# PatchPanel2015.net
KiCad netlist of a schematic drawn in EAGLE
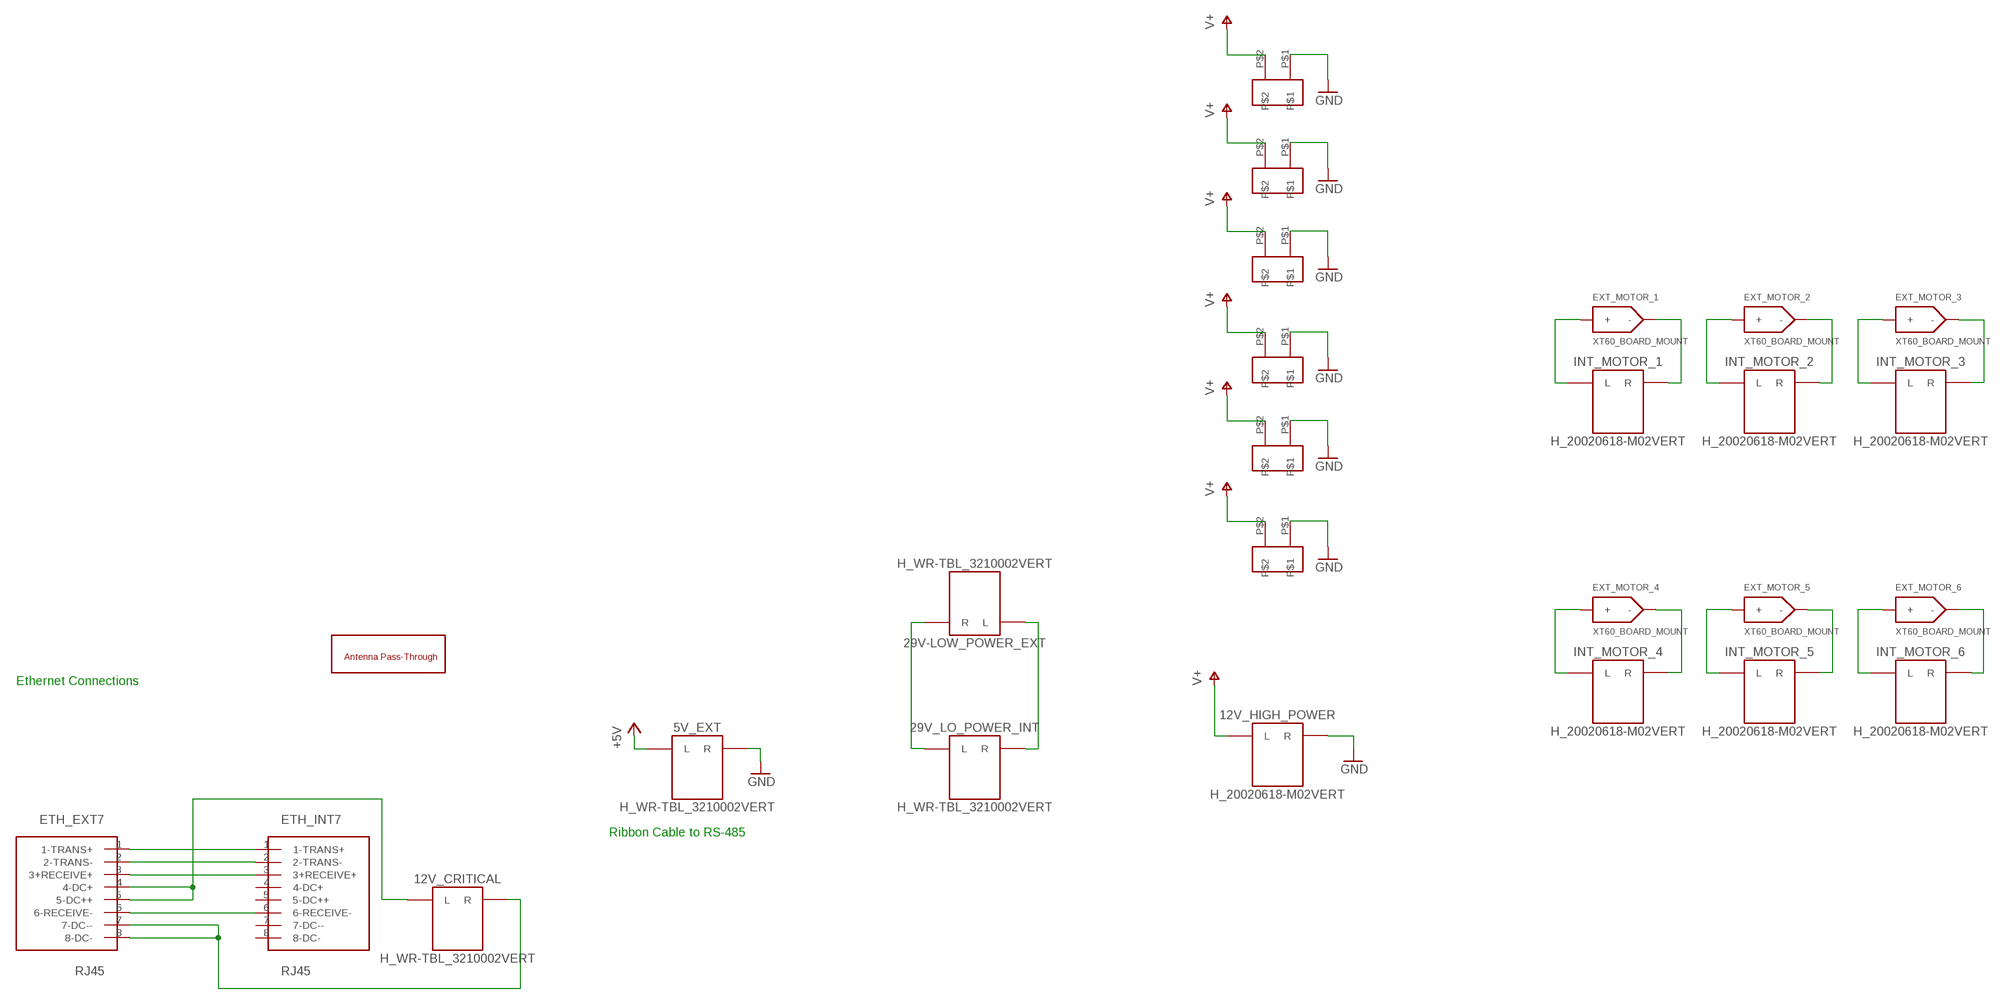
[diagram p0: schematic, sheet 1, part 1 of 2]
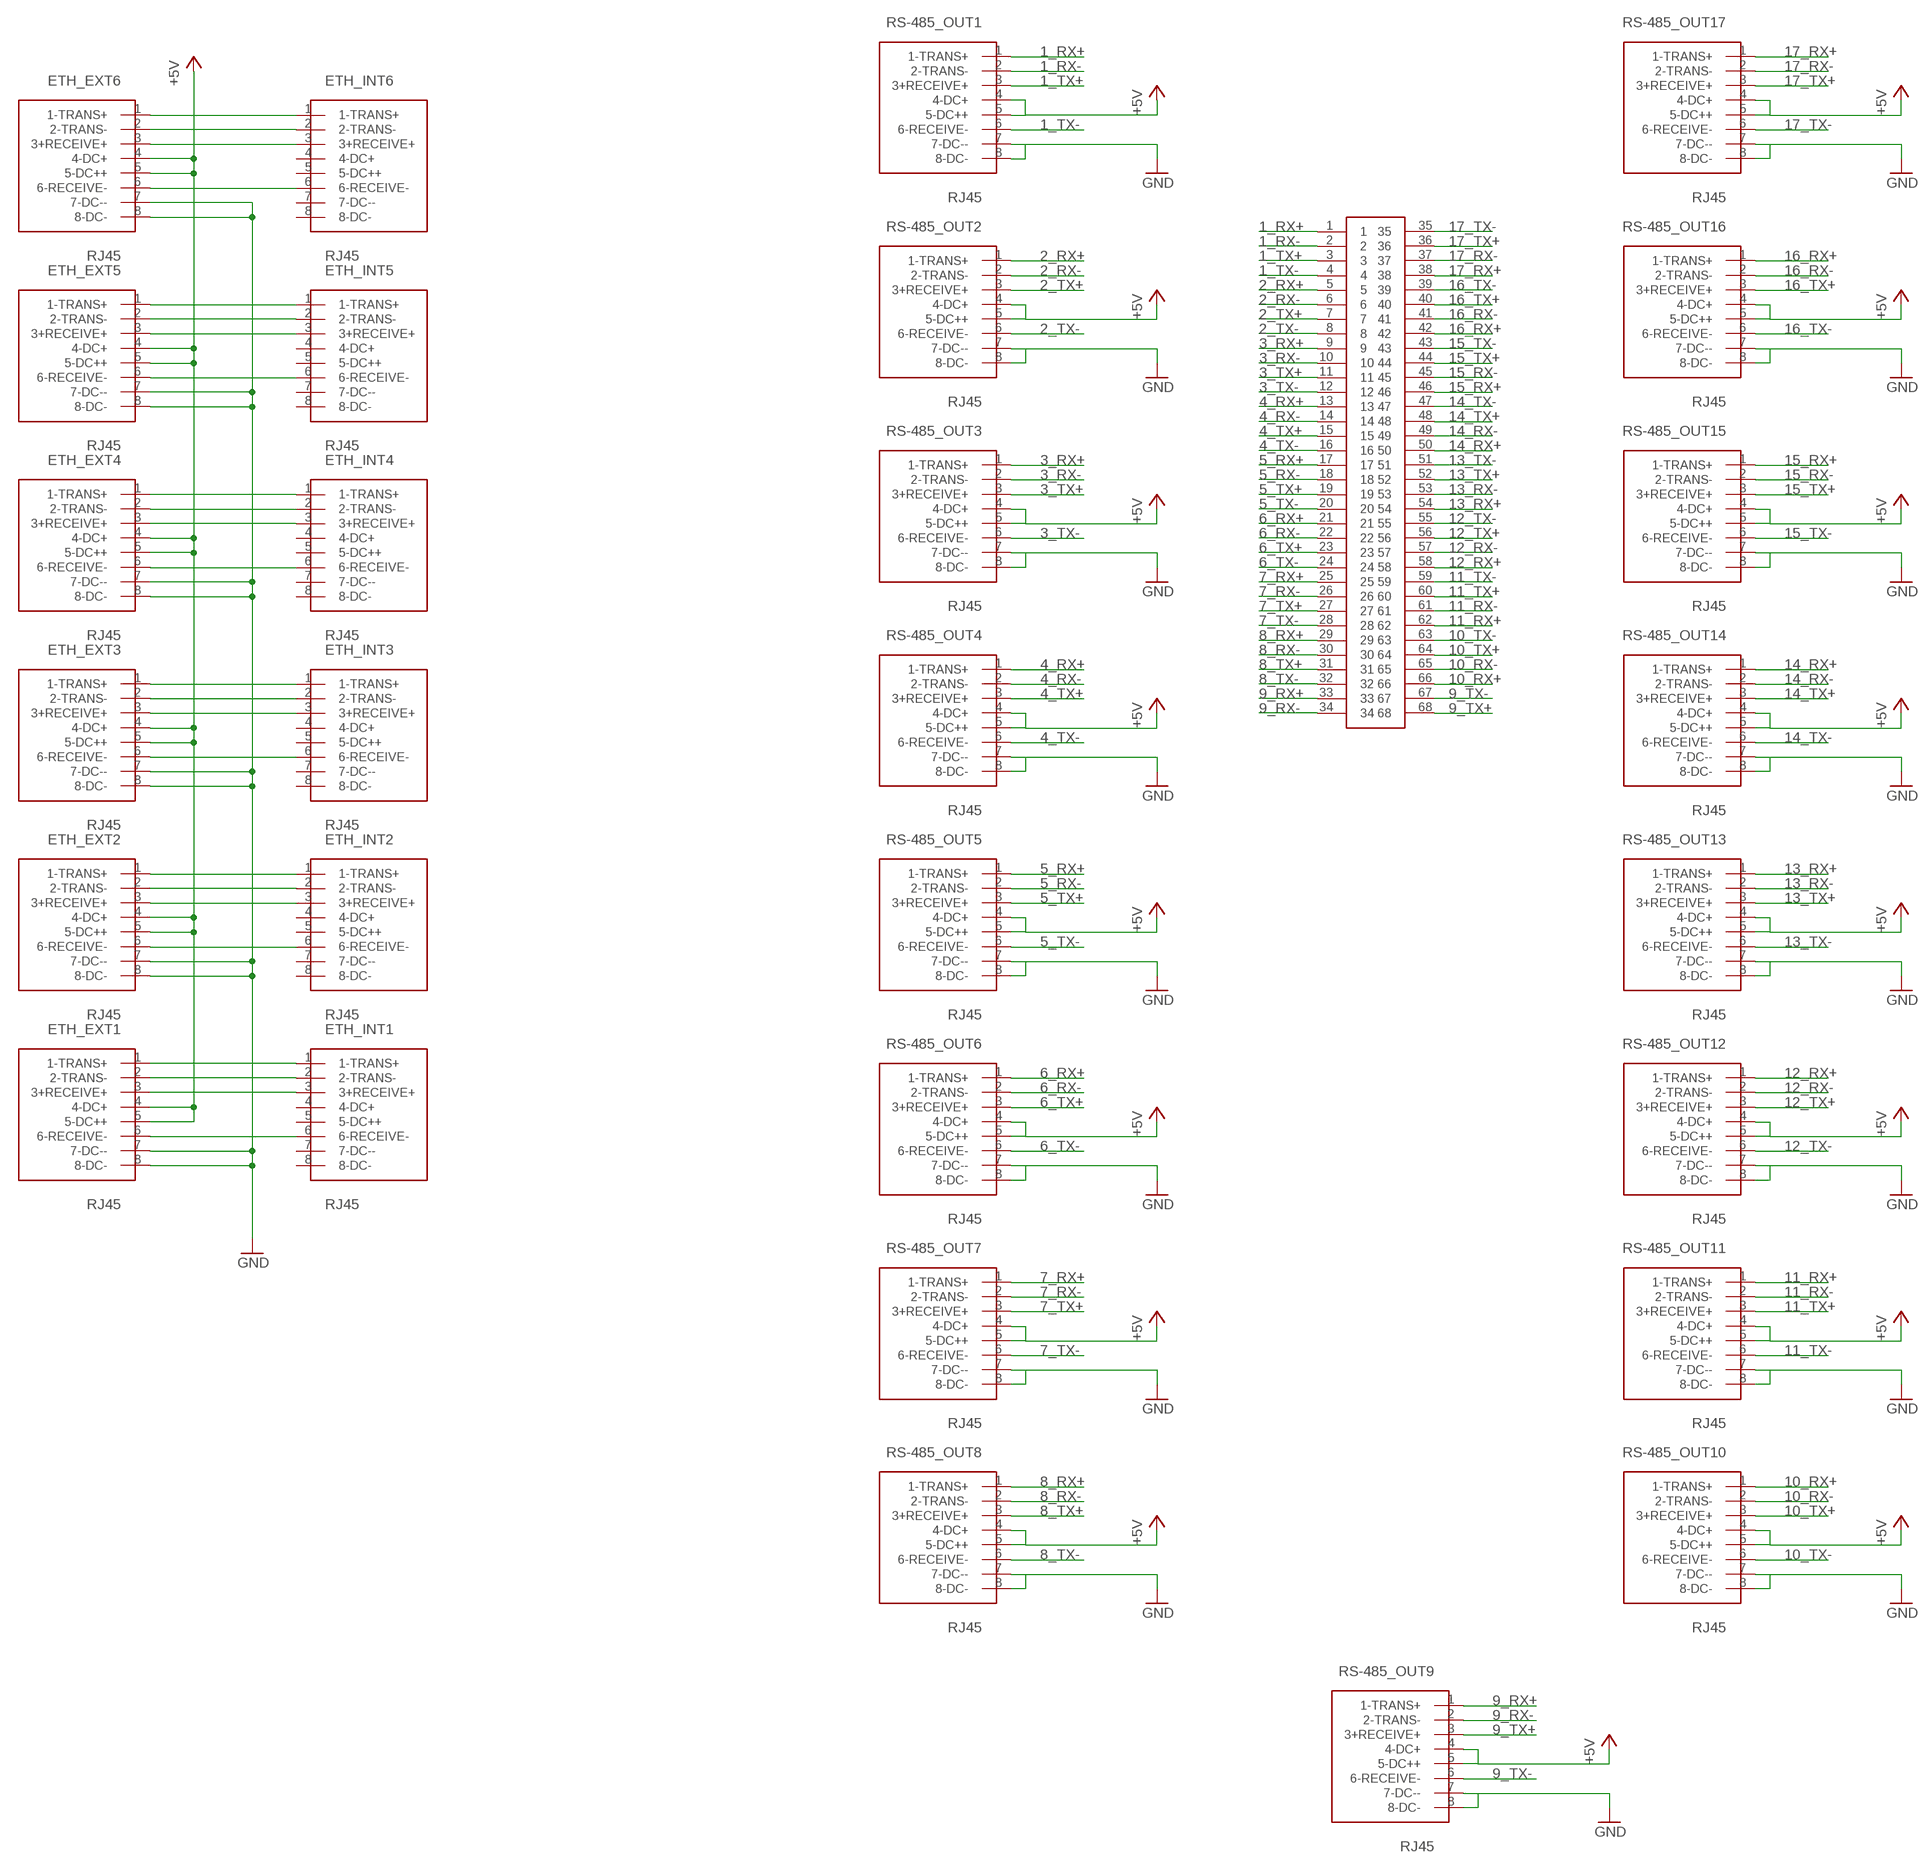
[diagram p1: schematic, sheet 1, part 2 of 2]

(export (version "E")
  (design (tool "Eeschema 10.0.6"))
  (components
    (comp (ref "5V_EXT")
      (value "H_WR-TBL_3210002VERT")
      (footprint "eagle-import:691321100002")
      (libsource (lib "eagle-import") (part "H_WR-TBL_3210002VERT"))
    )
    (comp (ref "12V_CRITICAL")
      (value "H_WR-TBL_3210002VERT")
      (footprint "eagle-import:691321100002")
      (libsource (lib "eagle-import") (part "H_WR-TBL_3210002VERT"))
    )
    (comp (ref "12V_HIGH_POWER")
      (value "H_20020618-M02VERT")
      (footprint "eagle-import:20020620-M02")
      (libsource (lib "eagle-import") (part "H_20020618-M02VERT"))
    )
    (comp (ref "29V-LOW_POWER_EXT")
      (value "H_WR-TBL_3210002VERT")
      (footprint "eagle-import:691321100002")
      (libsource (lib "eagle-import") (part "H_WR-TBL_3210002VERT"))
    )
    (comp (ref "29V_LO_POWER_INT")
      (value "H_WR-TBL_3210002VERT")
      (footprint "eagle-import:691321100002")
      (libsource (lib "eagle-import") (part "H_WR-TBL_3210002VERT"))
    )
    (comp (ref "ETH_EXT1")
      (value "RJ45")
      (footprint "eagle-import:RJ45-CAT5E")
      (libsource (lib "eagle-import") (part "RJ45"))
    )
    (comp (ref "ETH_EXT2")
      (value "RJ45")
      (footprint "eagle-import:RJ45-CAT5E")
      (libsource (lib "eagle-import") (part "RJ45"))
    )
    (comp (ref "ETH_EXT3")
      (value "RJ45")
      (footprint "eagle-import:RJ45-CAT5E")
      (libsource (lib "eagle-import") (part "RJ45"))
    )
    (comp (ref "ETH_EXT4")
      (value "RJ45")
      (footprint "eagle-import:RJ45-CAT5E")
      (libsource (lib "eagle-import") (part "RJ45"))
    )
    (comp (ref "ETH_EXT5")
      (value "RJ45")
      (footprint "eagle-import:RJ45-CAT5E")
      (libsource (lib "eagle-import") (part "RJ45"))
    )
    (comp (ref "ETH_EXT6")
      (value "RJ45")
      (footprint "eagle-import:RJ45-CAT5E")
      (libsource (lib "eagle-import") (part "RJ45"))
    )
    (comp (ref "ETH_EXT7")
      (value "RJ45")
      (footprint "eagle-import:RJ45-CAT5E")
      (libsource (lib "eagle-import") (part "RJ45"))
    )
    (comp (ref "ETH_INT1")
      (value "RJ45")
      (footprint "eagle-import:RJ45-CAT5E")
      (libsource (lib "eagle-import") (part "RJ45"))
    )
    (comp (ref "ETH_INT2")
      (value "RJ45")
      (footprint "eagle-import:RJ45-CAT5E")
      (libsource (lib "eagle-import") (part "RJ45"))
    )
    (comp (ref "ETH_INT3")
      (value "RJ45")
      (footprint "eagle-import:RJ45-CAT5E")
      (libsource (lib "eagle-import") (part "RJ45"))
    )
    (comp (ref "ETH_INT4")
      (value "RJ45")
      (footprint "eagle-import:RJ45-CAT5E")
      (libsource (lib "eagle-import") (part "RJ45"))
    )
    (comp (ref "ETH_INT5")
      (value "RJ45")
      (footprint "eagle-import:RJ45-CAT5E")
      (libsource (lib "eagle-import") (part "RJ45"))
    )
    (comp (ref "ETH_INT6")
      (value "RJ45")
      (footprint "eagle-import:RJ45-CAT5E")
      (libsource (lib "eagle-import") (part "RJ45"))
    )
    (comp (ref "ETH_INT7")
      (value "RJ45")
      (footprint "eagle-import:RJ45-CAT5E")
      (libsource (lib "eagle-import") (part "RJ45"))
    )
    (comp (ref "EXT_MOTOR_1")
      (value "XT60_BOARD_MOUNT")
      (footprint "eagle-import:XT60_BOARD")
      (libsource (lib "eagle-import") (part "XT60_BOARD_MOUNT"))
    )
    (comp (ref "EXT_MOTOR_2")
      (value "XT60_BOARD_MOUNT")
      (footprint "eagle-import:XT60_BOARD")
      (libsource (lib "eagle-import") (part "XT60_BOARD_MOUNT"))
    )
    (comp (ref "EXT_MOTOR_3")
      (value "XT60_BOARD_MOUNT")
      (footprint "eagle-import:XT60_BOARD")
      (libsource (lib "eagle-import") (part "XT60_BOARD_MOUNT"))
    )
    (comp (ref "EXT_MOTOR_4")
      (value "XT60_BOARD_MOUNT")
      (footprint "eagle-import:XT60_BOARD")
      (libsource (lib "eagle-import") (part "XT60_BOARD_MOUNT"))
    )
    (comp (ref "EXT_MOTOR_5")
      (value "XT60_BOARD_MOUNT")
      (footprint "eagle-import:XT60_BOARD")
      (libsource (lib "eagle-import") (part "XT60_BOARD_MOUNT"))
    )
    (comp (ref "EXT_MOTOR_6")
      (value "XT60_BOARD_MOUNT")
      (footprint "eagle-import:XT60_BOARD")
      (libsource (lib "eagle-import") (part "XT60_BOARD_MOUNT"))
    )
    (comp (ref "INT_MOTOR_1")
      (value "H_20020618-M02VERT")
      (footprint "eagle-import:20020620-M02")
      (libsource (lib "eagle-import") (part "H_20020618-M02VERT"))
    )
    (comp (ref "INT_MOTOR_2")
      (value "H_20020618-M02VERT")
      (footprint "eagle-import:20020620-M02")
      (libsource (lib "eagle-import") (part "H_20020618-M02VERT"))
    )
    (comp (ref "INT_MOTOR_3")
      (value "H_20020618-M02VERT")
      (footprint "eagle-import:20020620-M02")
      (libsource (lib "eagle-import") (part "H_20020618-M02VERT"))
    )
    (comp (ref "INT_MOTOR_4")
      (value "H_20020618-M02VERT")
      (footprint "eagle-import:20020620-M02")
      (libsource (lib "eagle-import") (part "H_20020618-M02VERT"))
    )
    (comp (ref "INT_MOTOR_5")
      (value "H_20020618-M02VERT")
      (footprint "eagle-import:20020620-M02")
      (libsource (lib "eagle-import") (part "H_20020618-M02VERT"))
    )
    (comp (ref "INT_MOTOR_6")
      (value "H_20020618-M02VERT")
      (footprint "eagle-import:20020620-M02")
      (libsource (lib "eagle-import") (part "H_20020618-M02VERT"))
    )
    (comp (ref "RS-485_OUT1")
      (value "RJ45")
      (footprint "eagle-import:RJ45-CAT5E")
      (libsource (lib "eagle-import") (part "RJ45"))
    )
    (comp (ref "RS-485_OUT2")
      (value "RJ45")
      (footprint "eagle-import:RJ45-CAT5E")
      (libsource (lib "eagle-import") (part "RJ45"))
    )
    (comp (ref "RS-485_OUT3")
      (value "RJ45")
      (footprint "eagle-import:RJ45-CAT5E")
      (libsource (lib "eagle-import") (part "RJ45"))
    )
    (comp (ref "RS-485_OUT4")
      (value "RJ45")
      (footprint "eagle-import:RJ45-CAT5E")
      (libsource (lib "eagle-import") (part "RJ45"))
    )
    (comp (ref "RS-485_OUT5")
      (value "RJ45")
      (footprint "eagle-import:RJ45-CAT5E")
      (libsource (lib "eagle-import") (part "RJ45"))
    )
    (comp (ref "RS-485_OUT6")
      (value "RJ45")
      (footprint "eagle-import:RJ45-CAT5E")
      (libsource (lib "eagle-import") (part "RJ45"))
    )
    (comp (ref "RS-485_OUT7")
      (value "RJ45")
      (footprint "eagle-import:RJ45-CAT5E")
      (libsource (lib "eagle-import") (part "RJ45"))
    )
    (comp (ref "RS-485_OUT8")
      (value "RJ45")
      (footprint "eagle-import:RJ45-CAT5E")
      (libsource (lib "eagle-import") (part "RJ45"))
    )
    (comp (ref "RS-485_OUT9")
      (value "RJ45")
      (footprint "eagle-import:RJ45-CAT5E")
      (libsource (lib "eagle-import") (part "RJ45"))
    )
    (comp (ref "RS-485_OUT10")
      (value "RJ45")
      (footprint "eagle-import:RJ45-CAT5E")
      (libsource (lib "eagle-import") (part "RJ45"))
    )
    (comp (ref "RS-485_OUT11")
      (value "RJ45")
      (footprint "eagle-import:RJ45-CAT5E")
      (libsource (lib "eagle-import") (part "RJ45"))
    )
    (comp (ref "RS-485_OUT12")
      (value "RJ45")
      (footprint "eagle-import:RJ45-CAT5E")
      (libsource (lib "eagle-import") (part "RJ45"))
    )
    (comp (ref "RS-485_OUT13")
      (value "RJ45")
      (footprint "eagle-import:RJ45-CAT5E")
      (libsource (lib "eagle-import") (part "RJ45"))
    )
    (comp (ref "RS-485_OUT14")
      (value "RJ45")
      (footprint "eagle-import:RJ45-CAT5E")
      (libsource (lib "eagle-import") (part "RJ45"))
    )
    (comp (ref "RS-485_OUT15")
      (value "RJ45")
      (footprint "eagle-import:RJ45-CAT5E")
      (libsource (lib "eagle-import") (part "RJ45"))
    )
    (comp (ref "RS-485_OUT16")
      (value "RJ45")
      (footprint "eagle-import:RJ45-CAT5E")
      (libsource (lib "eagle-import") (part "RJ45"))
    )
    (comp (ref "RS-485_OUT17")
      (value "RJ45")
      (footprint "eagle-import:RJ45-CAT5E")
      (libsource (lib "eagle-import") (part "RJ45"))
    )
    (comp (ref "U$1")
      (value "MLX-2")
      (footprint "eagle-import:42002-2")
      (libsource (lib "eagle-import") (part "MLX-2"))
    )
    (comp (ref "U$2")
      (value "MLX-2")
      (footprint "eagle-import:42002-2")
      (libsource (lib "eagle-import") (part "MLX-2"))
    )
    (comp (ref "U$3")
      (value "MLX-2")
      (footprint "eagle-import:42002-2")
      (libsource (lib "eagle-import") (part "MLX-2"))
    )
    (comp (ref "U$4")
      (value "TB60050685100")
      (footprint "eagle-import:60050685100")
      (libsource (lib "eagle-import") (part "TB60050685100"))
    )
    (comp (ref "U$5")
      (value "MLX-2")
      (footprint "eagle-import:42002-2")
      (libsource (lib "eagle-import") (part "MLX-2"))
    )
    (comp (ref "U$6")
      (value "MLX-2")
      (footprint "eagle-import:42002-2")
      (libsource (lib "eagle-import") (part "MLX-2"))
    )
    (comp (ref "U$8")
      (value "MLX-2")
      (footprint "eagle-import:42002-2")
      (libsource (lib "eagle-import") (part "MLX-2"))
    )
    (comp (ref "U$16")
      (value "SMA-THRU")
      (footprint "eagle-import:SMA")
      (libsource (lib "eagle-import") (part "SMA-THRU"))
    )
  )
  (nets
    (net (code "1") (name "+5V") (class "Default")
      (node (ref "5V_EXT") (pin "L") (pinfunction "L_L") (pintype "bidirectional"))
      (node (ref "ETH_EXT1") (pin "4") (pinfunction "4-DC+_4") (pintype "bidirectional"))
      (node (ref "ETH_EXT1") (pin "5") (pinfunction "5-DC++_5") (pintype "bidirectional"))
      (node (ref "ETH_EXT2") (pin "4") (pinfunction "4-DC+_4") (pintype "bidirectional"))
      (node (ref "ETH_EXT2") (pin "5") (pinfunction "5-DC++_5") (pintype "bidirectional"))
      (node (ref "ETH_EXT3") (pin "4") (pinfunction "4-DC+_4") (pintype "bidirectional"))
      (node (ref "ETH_EXT3") (pin "5") (pinfunction "5-DC++_5") (pintype "bidirectional"))
      (node (ref "ETH_EXT4") (pin "4") (pinfunction "4-DC+_4") (pintype "bidirectional"))
      (node (ref "ETH_EXT4") (pin "5") (pinfunction "5-DC++_5") (pintype "bidirectional"))
      (node (ref "ETH_EXT5") (pin "4") (pinfunction "4-DC+_4") (pintype "bidirectional"))
      (node (ref "ETH_EXT5") (pin "5") (pinfunction "5-DC++_5") (pintype "bidirectional"))
      (node (ref "ETH_EXT6") (pin "4") (pinfunction "4-DC+_4") (pintype "bidirectional"))
      (node (ref "ETH_EXT6") (pin "5") (pinfunction "5-DC++_5") (pintype "bidirectional"))
      (node (ref "RS-485_OUT1") (pin "4") (pinfunction "4-DC+_4") (pintype "bidirectional"))
      (node (ref "RS-485_OUT1") (pin "5") (pinfunction "5-DC++_5") (pintype "bidirectional"))
      (node (ref "RS-485_OUT10") (pin "4") (pinfunction "4-DC+_4") (pintype "bidirectional"))
      (node (ref "RS-485_OUT10") (pin "5") (pinfunction "5-DC++_5") (pintype "bidirectional"))
      (node (ref "RS-485_OUT11") (pin "4") (pinfunction "4-DC+_4") (pintype "bidirectional"))
      (node (ref "RS-485_OUT11") (pin "5") (pinfunction "5-DC++_5") (pintype "bidirectional"))
      (node (ref "RS-485_OUT12") (pin "4") (pinfunction "4-DC+_4") (pintype "bidirectional"))
      (node (ref "RS-485_OUT12") (pin "5") (pinfunction "5-DC++_5") (pintype "bidirectional"))
      (node (ref "RS-485_OUT13") (pin "4") (pinfunction "4-DC+_4") (pintype "bidirectional"))
      (node (ref "RS-485_OUT13") (pin "5") (pinfunction "5-DC++_5") (pintype "bidirectional"))
      (node (ref "RS-485_OUT14") (pin "4") (pinfunction "4-DC+_4") (pintype "bidirectional"))
      (node (ref "RS-485_OUT14") (pin "5") (pinfunction "5-DC++_5") (pintype "bidirectional"))
      (node (ref "RS-485_OUT15") (pin "4") (pinfunction "4-DC+_4") (pintype "bidirectional"))
      (node (ref "RS-485_OUT15") (pin "5") (pinfunction "5-DC++_5") (pintype "bidirectional"))
      (node (ref "RS-485_OUT16") (pin "4") (pinfunction "4-DC+_4") (pintype "bidirectional"))
      (node (ref "RS-485_OUT16") (pin "5") (pinfunction "5-DC++_5") (pintype "bidirectional"))
      (node (ref "RS-485_OUT17") (pin "4") (pinfunction "4-DC+_4") (pintype "bidirectional"))
      (node (ref "RS-485_OUT17") (pin "5") (pinfunction "5-DC++_5") (pintype "bidirectional"))
      (node (ref "RS-485_OUT2") (pin "4") (pinfunction "4-DC+_4") (pintype "bidirectional"))
      (node (ref "RS-485_OUT2") (pin "5") (pinfunction "5-DC++_5") (pintype "bidirectional"))
      (node (ref "RS-485_OUT3") (pin "4") (pinfunction "4-DC+_4") (pintype "bidirectional"))
      (node (ref "RS-485_OUT3") (pin "5") (pinfunction "5-DC++_5") (pintype "bidirectional"))
      (node (ref "RS-485_OUT4") (pin "4") (pinfunction "4-DC+_4") (pintype "bidirectional"))
      (node (ref "RS-485_OUT4") (pin "5") (pinfunction "5-DC++_5") (pintype "bidirectional"))
      (node (ref "RS-485_OUT5") (pin "4") (pinfunction "4-DC+_4") (pintype "bidirectional"))
      (node (ref "RS-485_OUT5") (pin "5") (pinfunction "5-DC++_5") (pintype "bidirectional"))
      (node (ref "RS-485_OUT6") (pin "4") (pinfunction "4-DC+_4") (pintype "bidirectional"))
      (node (ref "RS-485_OUT6") (pin "5") (pinfunction "5-DC++_5") (pintype "bidirectional"))
      (node (ref "RS-485_OUT7") (pin "4") (pinfunction "4-DC+_4") (pintype "bidirectional"))
      (node (ref "RS-485_OUT7") (pin "5") (pinfunction "5-DC++_5") (pintype "bidirectional"))
      (node (ref "RS-485_OUT8") (pin "4") (pinfunction "4-DC+_4") (pintype "bidirectional"))
      (node (ref "RS-485_OUT8") (pin "5") (pinfunction "5-DC++_5") (pintype "bidirectional"))
      (node (ref "RS-485_OUT9") (pin "4") (pinfunction "4-DC+_4") (pintype "bidirectional"))
      (node (ref "RS-485_OUT9") (pin "5") (pinfunction "5-DC++_5") (pintype "bidirectional"))
    )
    (net (code "2") (name "/1_RX+") (class "Default")
      (node (ref "RS-485_OUT1") (pin "1") (pinfunction "1-TRANS+_1") (pintype "bidirectional"))
      (node (ref "U$4") (pin "1") (pinfunction "1_1") (pintype "bidirectional"))
    )
    (net (code "3") (name "/1_RX-") (class "Default")
      (node (ref "RS-485_OUT1") (pin "2") (pinfunction "2-TRANS-_2") (pintype "bidirectional"))
      (node (ref "U$4") (pin "2") (pinfunction "2_2") (pintype "bidirectional"))
    )
    (net (code "4") (name "/1_TX+") (class "Default")
      (node (ref "RS-485_OUT1") (pin "3") (pinfunction "3+RECEIVE+_3") (pintype "bidirectional"))
      (node (ref "U$4") (pin "3") (pinfunction "3_3") (pintype "bidirectional"))
    )
    (net (code "5") (name "/1_TX-") (class "Default")
      (node (ref "RS-485_OUT1") (pin "6") (pinfunction "6-RECEIVE-_6") (pintype "bidirectional"))
      (node (ref "U$4") (pin "4") (pinfunction "4_4") (pintype "bidirectional"))
    )
    (net (code "6") (name "/2_RX+") (class "Default")
      (node (ref "RS-485_OUT2") (pin "1") (pinfunction "1-TRANS+_1") (pintype "bidirectional"))
      (node (ref "U$4") (pin "5") (pinfunction "5_5") (pintype "bidirectional"))
    )
    (net (code "7") (name "/2_RX-") (class "Default")
      (node (ref "RS-485_OUT2") (pin "2") (pinfunction "2-TRANS-_2") (pintype "bidirectional"))
      (node (ref "U$4") (pin "6") (pinfunction "6_6") (pintype "bidirectional"))
    )
    (net (code "8") (name "/2_TX+") (class "Default")
      (node (ref "RS-485_OUT2") (pin "3") (pinfunction "3+RECEIVE+_3") (pintype "bidirectional"))
      (node (ref "U$4") (pin "7") (pinfunction "7_7") (pintype "bidirectional"))
    )
    (net (code "9") (name "/2_TX-") (class "Default")
      (node (ref "RS-485_OUT2") (pin "6") (pinfunction "6-RECEIVE-_6") (pintype "bidirectional"))
      (node (ref "U$4") (pin "8") (pinfunction "8_8") (pintype "bidirectional"))
    )
    (net (code "10") (name "/3_RX+") (class "Default")
      (node (ref "RS-485_OUT3") (pin "1") (pinfunction "1-TRANS+_1") (pintype "bidirectional"))
      (node (ref "U$4") (pin "9") (pinfunction "9_9") (pintype "bidirectional"))
    )
    (net (code "11") (name "/3_RX-") (class "Default")
      (node (ref "RS-485_OUT3") (pin "2") (pinfunction "2-TRANS-_2") (pintype "bidirectional"))
      (node (ref "U$4") (pin "10") (pinfunction "10_10") (pintype "bidirectional"))
    )
    (net (code "12") (name "/3_TX+") (class "Default")
      (node (ref "RS-485_OUT3") (pin "3") (pinfunction "3+RECEIVE+_3") (pintype "bidirectional"))
      (node (ref "U$4") (pin "11") (pinfunction "11_11") (pintype "bidirectional"))
    )
    (net (code "13") (name "/3_TX-") (class "Default")
      (node (ref "RS-485_OUT3") (pin "6") (pinfunction "6-RECEIVE-_6") (pintype "bidirectional"))
      (node (ref "U$4") (pin "12") (pinfunction "12_12") (pintype "bidirectional"))
    )
    (net (code "14") (name "/4_RX+") (class "Default")
      (node (ref "RS-485_OUT4") (pin "1") (pinfunction "1-TRANS+_1") (pintype "bidirectional"))
      (node (ref "U$4") (pin "13") (pinfunction "13_13") (pintype "bidirectional"))
    )
    (net (code "15") (name "/4_RX-") (class "Default")
      (node (ref "RS-485_OUT4") (pin "2") (pinfunction "2-TRANS-_2") (pintype "bidirectional"))
      (node (ref "U$4") (pin "14") (pinfunction "14_14") (pintype "bidirectional"))
    )
    (net (code "16") (name "/4_TX+") (class "Default")
      (node (ref "RS-485_OUT4") (pin "3") (pinfunction "3+RECEIVE+_3") (pintype "bidirectional"))
      (node (ref "U$4") (pin "15") (pinfunction "15_15") (pintype "bidirectional"))
    )
    (net (code "17") (name "/4_TX-") (class "Default")
      (node (ref "RS-485_OUT4") (pin "6") (pinfunction "6-RECEIVE-_6") (pintype "bidirectional"))
      (node (ref "U$4") (pin "16") (pinfunction "16_16") (pintype "bidirectional"))
    )
    (net (code "18") (name "/5_RX+") (class "Default")
      (node (ref "RS-485_OUT5") (pin "1") (pinfunction "1-TRANS+_1") (pintype "bidirectional"))
      (node (ref "U$4") (pin "17") (pinfunction "17_17") (pintype "bidirectional"))
    )
    (net (code "19") (name "/5_RX-") (class "Default")
      (node (ref "RS-485_OUT5") (pin "2") (pinfunction "2-TRANS-_2") (pintype "bidirectional"))
      (node (ref "U$4") (pin "18") (pinfunction "18_18") (pintype "bidirectional"))
    )
    (net (code "20") (name "/5_TX+") (class "Default")
      (node (ref "RS-485_OUT5") (pin "3") (pinfunction "3+RECEIVE+_3") (pintype "bidirectional"))
      (node (ref "U$4") (pin "19") (pinfunction "19_19") (pintype "bidirectional"))
    )
    (net (code "21") (name "/5_TX-") (class "Default")
      (node (ref "RS-485_OUT5") (pin "6") (pinfunction "6-RECEIVE-_6") (pintype "bidirectional"))
      (node (ref "U$4") (pin "20") (pinfunction "20_20") (pintype "bidirectional"))
    )
    (net (code "22") (name "/6_RX+") (class "Default")
      (node (ref "RS-485_OUT6") (pin "1") (pinfunction "1-TRANS+_1") (pintype "bidirectional"))
      (node (ref "U$4") (pin "21") (pinfunction "21_21") (pintype "bidirectional"))
    )
    (net (code "23") (name "/6_RX-") (class "Default")
      (node (ref "RS-485_OUT6") (pin "2") (pinfunction "2-TRANS-_2") (pintype "bidirectional"))
      (node (ref "U$4") (pin "22") (pinfunction "22_22") (pintype "bidirectional"))
    )
    (net (code "24") (name "/6_TX+") (class "Default")
      (node (ref "RS-485_OUT6") (pin "3") (pinfunction "3+RECEIVE+_3") (pintype "bidirectional"))
      (node (ref "U$4") (pin "23") (pinfunction "23_23") (pintype "bidirectional"))
    )
    (net (code "25") (name "/6_TX-") (class "Default")
      (node (ref "RS-485_OUT6") (pin "6") (pinfunction "6-RECEIVE-_6") (pintype "bidirectional"))
      (node (ref "U$4") (pin "24") (pinfunction "24_24") (pintype "bidirectional"))
    )
    (net (code "26") (name "/7_RX+") (class "Default")
      (node (ref "RS-485_OUT7") (pin "1") (pinfunction "1-TRANS+_1") (pintype "bidirectional"))
      (node (ref "U$4") (pin "25") (pinfunction "25_25") (pintype "bidirectional"))
    )
    (net (code "27") (name "/7_RX-") (class "Default")
      (node (ref "RS-485_OUT7") (pin "2") (pinfunction "2-TRANS-_2") (pintype "bidirectional"))
      (node (ref "U$4") (pin "26") (pinfunction "26_26") (pintype "bidirectional"))
    )
    (net (code "28") (name "/7_TX+") (class "Default")
      (node (ref "RS-485_OUT7") (pin "3") (pinfunction "3+RECEIVE+_3") (pintype "bidirectional"))
      (node (ref "U$4") (pin "27") (pinfunction "27_27") (pintype "bidirectional"))
    )
    (net (code "29") (name "/7_TX-") (class "Default")
      (node (ref "RS-485_OUT7") (pin "6") (pinfunction "6-RECEIVE-_6") (pintype "bidirectional"))
      (node (ref "U$4") (pin "28") (pinfunction "28_28") (pintype "bidirectional"))
    )
    (net (code "30") (name "/8_RX+") (class "Default")
      (node (ref "RS-485_OUT8") (pin "1") (pinfunction "1-TRANS+_1") (pintype "bidirectional"))
      (node (ref "U$4") (pin "29") (pinfunction "29_29") (pintype "bidirectional"))
    )
    (net (code "31") (name "/8_RX-") (class "Default")
      (node (ref "RS-485_OUT8") (pin "2") (pinfunction "2-TRANS-_2") (pintype "bidirectional"))
      (node (ref "U$4") (pin "30") (pinfunction "30_30") (pintype "bidirectional"))
    )
    (net (code "32") (name "/8_TX+") (class "Default")
      (node (ref "RS-485_OUT8") (pin "3") (pinfunction "3+RECEIVE+_3") (pintype "bidirectional"))
      (node (ref "U$4") (pin "31") (pinfunction "31_31") (pintype "bidirectional"))
    )
    (net (code "33") (name "/8_TX-") (class "Default")
      (node (ref "RS-485_OUT8") (pin "6") (pinfunction "6-RECEIVE-_6") (pintype "bidirectional"))
      (node (ref "U$4") (pin "32") (pinfunction "32_32") (pintype "bidirectional"))
    )
    (net (code "34") (name "/9_RX+") (class "Default")
      (node (ref "RS-485_OUT9") (pin "1") (pinfunction "1-TRANS+_1") (pintype "bidirectional"))
      (node (ref "U$4") (pin "33") (pinfunction "33_33") (pintype "bidirectional"))
    )
    (net (code "35") (name "/9_RX-") (class "Default")
      (node (ref "RS-485_OUT9") (pin "2") (pinfunction "2-TRANS-_2") (pintype "bidirectional"))
      (node (ref "U$4") (pin "34") (pinfunction "34_34") (pintype "bidirectional"))
    )
    (net (code "36") (name "/9_TX+") (class "Default")
      (node (ref "RS-485_OUT9") (pin "3") (pinfunction "3+RECEIVE+_3") (pintype "bidirectional"))
      (node (ref "U$4") (pin "68") (pinfunction "68_68") (pintype "bidirectional"))
    )
    (net (code "37") (name "/9_TX-") (class "Default")
      (node (ref "RS-485_OUT9") (pin "6") (pinfunction "6-RECEIVE-_6") (pintype "bidirectional"))
      (node (ref "U$4") (pin "67") (pinfunction "67_67") (pintype "bidirectional"))
    )
    (net (code "38") (name "/10_RX+") (class "Default")
      (node (ref "RS-485_OUT10") (pin "1") (pinfunction "1-TRANS+_1") (pintype "bidirectional"))
      (node (ref "U$4") (pin "66") (pinfunction "66_66") (pintype "bidirectional"))
    )
    (net (code "39") (name "/10_RX-") (class "Default")
      (node (ref "RS-485_OUT10") (pin "2") (pinfunction "2-TRANS-_2") (pintype "bidirectional"))
      (node (ref "U$4") (pin "65") (pinfunction "65_65") (pintype "bidirectional"))
    )
    (net (code "40") (name "/10_TX+") (class "Default")
      (node (ref "RS-485_OUT10") (pin "3") (pinfunction "3+RECEIVE+_3") (pintype "bidirectional"))
      (node (ref "U$4") (pin "64") (pinfunction "64_64") (pintype "bidirectional"))
    )
    (net (code "41") (name "/10_TX-") (class "Default")
      (node (ref "RS-485_OUT10") (pin "6") (pinfunction "6-RECEIVE-_6") (pintype "bidirectional"))
      (node (ref "U$4") (pin "63") (pinfunction "63_63") (pintype "bidirectional"))
    )
    (net (code "42") (name "/11_RX+") (class "Default")
      (node (ref "RS-485_OUT11") (pin "1") (pinfunction "1-TRANS+_1") (pintype "bidirectional"))
      (node (ref "U$4") (pin "62") (pinfunction "62_62") (pintype "bidirectional"))
    )
    (net (code "43") (name "/11_RX-") (class "Default")
      (node (ref "RS-485_OUT11") (pin "2") (pinfunction "2-TRANS-_2") (pintype "bidirectional"))
      (node (ref "U$4") (pin "61") (pinfunction "61_61") (pintype "bidirectional"))
    )
    (net (code "44") (name "/11_TX+") (class "Default")
      (node (ref "RS-485_OUT11") (pin "3") (pinfunction "3+RECEIVE+_3") (pintype "bidirectional"))
      (node (ref "U$4") (pin "60") (pinfunction "60_60") (pintype "bidirectional"))
    )
    (net (code "45") (name "/11_TX-") (class "Default")
      (node (ref "RS-485_OUT11") (pin "6") (pinfunction "6-RECEIVE-_6") (pintype "bidirectional"))
      (node (ref "U$4") (pin "59") (pinfunction "59_59") (pintype "bidirectional"))
    )
    (net (code "46") (name "/12_RX+") (class "Default")
      (node (ref "RS-485_OUT12") (pin "1") (pinfunction "1-TRANS+_1") (pintype "bidirectional"))
      (node (ref "U$4") (pin "58") (pinfunction "58_58") (pintype "bidirectional"))
    )
    (net (code "47") (name "/12_RX-") (class "Default")
      (node (ref "RS-485_OUT12") (pin "2") (pinfunction "2-TRANS-_2") (pintype "bidirectional"))
      (node (ref "U$4") (pin "57") (pinfunction "57_57") (pintype "bidirectional"))
    )
    (net (code "48") (name "/12_TX+") (class "Default")
      (node (ref "RS-485_OUT12") (pin "3") (pinfunction "3+RECEIVE+_3") (pintype "bidirectional"))
      (node (ref "U$4") (pin "56") (pinfunction "56_56") (pintype "bidirectional"))
    )
    (net (code "49") (name "/12_TX-") (class "Default")
      (node (ref "RS-485_OUT12") (pin "6") (pinfunction "6-RECEIVE-_6") (pintype "bidirectional"))
      (node (ref "U$4") (pin "55") (pinfunction "55_55") (pintype "bidirectional"))
    )
    (net (code "50") (name "/13_RX+") (class "Default")
      (node (ref "RS-485_OUT13") (pin "1") (pinfunction "1-TRANS+_1") (pintype "bidirectional"))
      (node (ref "U$4") (pin "54") (pinfunction "54_54") (pintype "bidirectional"))
    )
    (net (code "51") (name "/13_RX-") (class "Default")
      (node (ref "RS-485_OUT13") (pin "2") (pinfunction "2-TRANS-_2") (pintype "bidirectional"))
      (node (ref "U$4") (pin "53") (pinfunction "53_53") (pintype "bidirectional"))
    )
    (net (code "52") (name "/13_TX+") (class "Default")
      (node (ref "RS-485_OUT13") (pin "3") (pinfunction "3+RECEIVE+_3") (pintype "bidirectional"))
      (node (ref "U$4") (pin "52") (pinfunction "52_52") (pintype "bidirectional"))
    )
    (net (code "53") (name "/13_TX-") (class "Default")
      (node (ref "RS-485_OUT13") (pin "6") (pinfunction "6-RECEIVE-_6") (pintype "bidirectional"))
      (node (ref "U$4") (pin "51") (pinfunction "51_51") (pintype "bidirectional"))
    )
    (net (code "54") (name "/14_RX+") (class "Default")
      (node (ref "RS-485_OUT14") (pin "1") (pinfunction "1-TRANS+_1") (pintype "bidirectional"))
      (node (ref "U$4") (pin "50") (pinfunction "50_50") (pintype "bidirectional"))
    )
    (net (code "55") (name "/14_RX-") (class "Default")
      (node (ref "RS-485_OUT14") (pin "2") (pinfunction "2-TRANS-_2") (pintype "bidirectional"))
      (node (ref "U$4") (pin "49") (pinfunction "49_49") (pintype "bidirectional"))
    )
    (net (code "56") (name "/14_TX+") (class "Default")
      (node (ref "RS-485_OUT14") (pin "3") (pinfunction "3+RECEIVE+_3") (pintype "bidirectional"))
      (node (ref "U$4") (pin "48") (pinfunction "48_48") (pintype "bidirectional"))
    )
    (net (code "57") (name "/14_TX-") (class "Default")
      (node (ref "RS-485_OUT14") (pin "6") (pinfunction "6-RECEIVE-_6") (pintype "bidirectional"))
      (node (ref "U$4") (pin "47") (pinfunction "47_47") (pintype "bidirectional"))
    )
    (net (code "58") (name "/15_RX+") (class "Default")
      (node (ref "RS-485_OUT15") (pin "1") (pinfunction "1-TRANS+_1") (pintype "bidirectional"))
      (node (ref "U$4") (pin "46") (pinfunction "46_46") (pintype "bidirectional"))
    )
    (net (code "59") (name "/15_RX-") (class "Default")
      (node (ref "RS-485_OUT15") (pin "2") (pinfunction "2-TRANS-_2") (pintype "bidirectional"))
      (node (ref "U$4") (pin "45") (pinfunction "45_45") (pintype "bidirectional"))
    )
    (net (code "60") (name "/15_TX+") (class "Default")
      (node (ref "RS-485_OUT15") (pin "3") (pinfunction "3+RECEIVE+_3") (pintype "bidirectional"))
      (node (ref "U$4") (pin "44") (pinfunction "44_44") (pintype "bidirectional"))
    )
    (net (code "61") (name "/15_TX-") (class "Default")
      (node (ref "RS-485_OUT15") (pin "6") (pinfunction "6-RECEIVE-_6") (pintype "bidirectional"))
      (node (ref "U$4") (pin "43") (pinfunction "43_43") (pintype "bidirectional"))
    )
    (net (code "62") (name "/16_RX+") (class "Default")
      (node (ref "RS-485_OUT16") (pin "1") (pinfunction "1-TRANS+_1") (pintype "bidirectional"))
      (node (ref "U$4") (pin "42") (pinfunction "42_42") (pintype "bidirectional"))
    )
    (net (code "63") (name "/16_RX-") (class "Default")
      (node (ref "RS-485_OUT16") (pin "2") (pinfunction "2-TRANS-_2") (pintype "bidirectional"))
      (node (ref "U$4") (pin "41") (pinfunction "41_41") (pintype "bidirectional"))
    )
    (net (code "64") (name "/16_TX+") (class "Default")
      (node (ref "RS-485_OUT16") (pin "3") (pinfunction "3+RECEIVE+_3") (pintype "bidirectional"))
      (node (ref "U$4") (pin "40") (pinfunction "40_40") (pintype "bidirectional"))
    )
    (net (code "65") (name "/16_TX-") (class "Default")
      (node (ref "RS-485_OUT16") (pin "6") (pinfunction "6-RECEIVE-_6") (pintype "bidirectional"))
      (node (ref "U$4") (pin "39") (pinfunction "39_39") (pintype "bidirectional"))
    )
    (net (code "66") (name "/17_RX+") (class "Default")
      (node (ref "RS-485_OUT17") (pin "1") (pinfunction "1-TRANS+_1") (pintype "bidirectional"))
      (node (ref "U$4") (pin "38") (pinfunction "38_38") (pintype "bidirectional"))
    )
    (net (code "67") (name "/17_RX-") (class "Default")
      (node (ref "RS-485_OUT17") (pin "2") (pinfunction "2-TRANS-_2") (pintype "bidirectional"))
      (node (ref "U$4") (pin "37") (pinfunction "37_37") (pintype "bidirectional"))
    )
    (net (code "68") (name "/17_TX+") (class "Default")
      (node (ref "RS-485_OUT17") (pin "3") (pinfunction "3+RECEIVE+_3") (pintype "bidirectional"))
      (node (ref "U$4") (pin "36") (pinfunction "36_36") (pintype "bidirectional"))
    )
    (net (code "69") (name "/17_TX-") (class "Default")
      (node (ref "RS-485_OUT17") (pin "6") (pinfunction "6-RECEIVE-_6") (pintype "bidirectional"))
      (node (ref "U$4") (pin "35") (pinfunction "35_35") (pintype "bidirectional"))
    )
    (net (code "70") (name "GND") (class "Default")
      (node (ref "12V_HIGH_POWER") (pin "R1") (pinfunction "R_R1") (pintype "bidirectional"))
      (node (ref "12V_HIGH_POWER") (pin "R2") (pinfunction "R_R2") (pintype "bidirectional"))
      (node (ref "5V_EXT") (pin "R") (pinfunction "R_R") (pintype "bidirectional"))
      (node (ref "ETH_EXT1") (pin "7") (pinfunction "7-DC--_7") (pintype "bidirectional"))
      (node (ref "ETH_EXT1") (pin "8") (pinfunction "8-DC-_8") (pintype "bidirectional"))
      (node (ref "ETH_EXT2") (pin "7") (pinfunction "7-DC--_7") (pintype "bidirectional"))
      (node (ref "ETH_EXT2") (pin "8") (pinfunction "8-DC-_8") (pintype "bidirectional"))
      (node (ref "ETH_EXT3") (pin "7") (pinfunction "7-DC--_7") (pintype "bidirectional"))
      (node (ref "ETH_EXT3") (pin "8") (pinfunction "8-DC-_8") (pintype "bidirectional"))
      (node (ref "ETH_EXT4") (pin "7") (pinfunction "7-DC--_7") (pintype "bidirectional"))
      (node (ref "ETH_EXT4") (pin "8") (pinfunction "8-DC-_8") (pintype "bidirectional"))
      (node (ref "ETH_EXT5") (pin "7") (pinfunction "7-DC--_7") (pintype "bidirectional"))
      (node (ref "ETH_EXT5") (pin "8") (pinfunction "8-DC-_8") (pintype "bidirectional"))
      (node (ref "ETH_EXT6") (pin "7") (pinfunction "7-DC--_7") (pintype "bidirectional"))
      (node (ref "ETH_EXT6") (pin "8") (pinfunction "8-DC-_8") (pintype "bidirectional"))
      (node (ref "RS-485_OUT1") (pin "7") (pinfunction "7-DC--_7") (pintype "bidirectional"))
      (node (ref "RS-485_OUT1") (pin "8") (pinfunction "8-DC-_8") (pintype "bidirectional"))
      (node (ref "RS-485_OUT10") (pin "7") (pinfunction "7-DC--_7") (pintype "bidirectional"))
      (node (ref "RS-485_OUT10") (pin "8") (pinfunction "8-DC-_8") (pintype "bidirectional"))
      (node (ref "RS-485_OUT11") (pin "7") (pinfunction "7-DC--_7") (pintype "bidirectional"))
      (node (ref "RS-485_OUT11") (pin "8") (pinfunction "8-DC-_8") (pintype "bidirectional"))
      (node (ref "RS-485_OUT12") (pin "7") (pinfunction "7-DC--_7") (pintype "bidirectional"))
      (node (ref "RS-485_OUT12") (pin "8") (pinfunction "8-DC-_8") (pintype "bidirectional"))
      (node (ref "RS-485_OUT13") (pin "7") (pinfunction "7-DC--_7") (pintype "bidirectional"))
      (node (ref "RS-485_OUT13") (pin "8") (pinfunction "8-DC-_8") (pintype "bidirectional"))
      (node (ref "RS-485_OUT14") (pin "7") (pinfunction "7-DC--_7") (pintype "bidirectional"))
      (node (ref "RS-485_OUT14") (pin "8") (pinfunction "8-DC-_8") (pintype "bidirectional"))
      (node (ref "RS-485_OUT15") (pin "7") (pinfunction "7-DC--_7") (pintype "bidirectional"))
      (node (ref "RS-485_OUT15") (pin "8") (pinfunction "8-DC-_8") (pintype "bidirectional"))
      (node (ref "RS-485_OUT16") (pin "7") (pinfunction "7-DC--_7") (pintype "bidirectional"))
      (node (ref "RS-485_OUT16") (pin "8") (pinfunction "8-DC-_8") (pintype "bidirectional"))
      (node (ref "RS-485_OUT17") (pin "7") (pinfunction "7-DC--_7") (pintype "bidirectional"))
      (node (ref "RS-485_OUT17") (pin "8") (pinfunction "8-DC-_8") (pintype "bidirectional"))
      (node (ref "RS-485_OUT2") (pin "7") (pinfunction "7-DC--_7") (pintype "bidirectional"))
      (node (ref "RS-485_OUT2") (pin "8") (pinfunction "8-DC-_8") (pintype "bidirectional"))
      (node (ref "RS-485_OUT3") (pin "7") (pinfunction "7-DC--_7") (pintype "bidirectional"))
      (node (ref "RS-485_OUT3") (pin "8") (pinfunction "8-DC-_8") (pintype "bidirectional"))
      (node (ref "RS-485_OUT4") (pin "7") (pinfunction "7-DC--_7") (pintype "bidirectional"))
      (node (ref "RS-485_OUT4") (pin "8") (pinfunction "8-DC-_8") (pintype "bidirectional"))
      (node (ref "RS-485_OUT5") (pin "7") (pinfunction "7-DC--_7") (pintype "bidirectional"))
      (node (ref "RS-485_OUT5") (pin "8") (pinfunction "8-DC-_8") (pintype "bidirectional"))
      (node (ref "RS-485_OUT6") (pin "7") (pinfunction "7-DC--_7") (pintype "bidirectional"))
      (node (ref "RS-485_OUT6") (pin "8") (pinfunction "8-DC-_8") (pintype "bidirectional"))
      (node (ref "RS-485_OUT7") (pin "7") (pinfunction "7-DC--_7") (pintype "bidirectional"))
      (node (ref "RS-485_OUT7") (pin "8") (pinfunction "8-DC-_8") (pintype "bidirectional"))
      (node (ref "RS-485_OUT8") (pin "7") (pinfunction "7-DC--_7") (pintype "bidirectional"))
      (node (ref "RS-485_OUT8") (pin "8") (pinfunction "8-DC-_8") (pintype "bidirectional"))
      (node (ref "RS-485_OUT9") (pin "7") (pinfunction "7-DC--_7") (pintype "bidirectional"))
      (node (ref "RS-485_OUT9") (pin "8") (pinfunction "8-DC-_8") (pintype "bidirectional"))
      (node (ref "U$1") (pin "P$1") (pinfunction "P$1_P$1") (pintype "bidirectional"))
      (node (ref "U$2") (pin "P$1") (pinfunction "P$1_P$1") (pintype "bidirectional"))
      (node (ref "U$3") (pin "P$1") (pinfunction "P$1_P$1") (pintype "bidirectional"))
      (node (ref "U$5") (pin "P$1") (pinfunction "P$1_P$1") (pintype "bidirectional"))
      (node (ref "U$6") (pin "P$1") (pinfunction "P$1_P$1") (pintype "bidirectional"))
      (node (ref "U$8") (pin "P$1") (pinfunction "P$1_P$1") (pintype "bidirectional"))
    )
    (net (code "71") (name "Net-(29V-LOW_POWER_EXT-PadL)") (class "Default")
      (node (ref "29V-LOW_POWER_EXT") (pin "L") (pinfunction "L_L") (pintype "bidirectional"))
      (node (ref "29V_LO_POWER_INT") (pin "R") (pinfunction "R_R") (pintype "bidirectional"))
    )
    (net (code "72") (name "Net-(29V-LOW_POWER_EXT-PadR)") (class "Default")
      (node (ref "29V-LOW_POWER_EXT") (pin "R") (pinfunction "R_R") (pintype "bidirectional"))
      (node (ref "29V_LO_POWER_INT") (pin "L") (pinfunction "L_L") (pintype "bidirectional"))
    )
    (net (code "73") (name "Net-(ETH_EXT1-1-TRANS+)") (class "Default")
      (node (ref "ETH_EXT1") (pin "1") (pinfunction "1-TRANS+_1") (pintype "bidirectional"))
      (node (ref "ETH_INT1") (pin "1") (pinfunction "1-TRANS+_1") (pintype "bidirectional"))
    )
    (net (code "74") (name "Net-(ETH_EXT1-2-TRANS-)") (class "Default")
      (node (ref "ETH_EXT1") (pin "2") (pinfunction "2-TRANS-_2") (pintype "bidirectional"))
      (node (ref "ETH_INT1") (pin "2") (pinfunction "2-TRANS-_2") (pintype "bidirectional"))
    )
    (net (code "75") (name "Net-(ETH_EXT1-3+RECEIVE+)") (class "Default")
      (node (ref "ETH_EXT1") (pin "3") (pinfunction "3+RECEIVE+_3") (pintype "bidirectional"))
      (node (ref "ETH_INT1") (pin "3") (pinfunction "3+RECEIVE+_3") (pintype "bidirectional"))
    )
    (net (code "76") (name "Net-(ETH_EXT1-6-RECEIVE-)") (class "Default")
      (node (ref "ETH_EXT1") (pin "6") (pinfunction "6-RECEIVE-_6") (pintype "bidirectional"))
      (node (ref "ETH_INT1") (pin "6") (pinfunction "6-RECEIVE-_6") (pintype "bidirectional"))
    )
    (net (code "77") (name "Net-(ETH_EXT2-1-TRANS+)") (class "Default")
      (node (ref "ETH_EXT2") (pin "1") (pinfunction "1-TRANS+_1") (pintype "bidirectional"))
      (node (ref "ETH_INT2") (pin "1") (pinfunction "1-TRANS+_1") (pintype "bidirectional"))
    )
    (net (code "78") (name "Net-(ETH_EXT2-2-TRANS-)") (class "Default")
      (node (ref "ETH_EXT2") (pin "2") (pinfunction "2-TRANS-_2") (pintype "bidirectional"))
      (node (ref "ETH_INT2") (pin "2") (pinfunction "2-TRANS-_2") (pintype "bidirectional"))
    )
    (net (code "79") (name "Net-(ETH_EXT2-3+RECEIVE+)") (class "Default")
      (node (ref "ETH_EXT2") (pin "3") (pinfunction "3+RECEIVE+_3") (pintype "bidirectional"))
      (node (ref "ETH_INT2") (pin "3") (pinfunction "3+RECEIVE+_3") (pintype "bidirectional"))
    )
    (net (code "80") (name "Net-(ETH_EXT2-6-RECEIVE-)") (class "Default")
      (node (ref "ETH_EXT2") (pin "6") (pinfunction "6-RECEIVE-_6") (pintype "bidirectional"))
      (node (ref "ETH_INT2") (pin "6") (pinfunction "6-RECEIVE-_6") (pintype "bidirectional"))
    )
    (net (code "81") (name "Net-(ETH_EXT3-1-TRANS+)") (class "Default")
      (node (ref "ETH_EXT3") (pin "1") (pinfunction "1-TRANS+_1") (pintype "bidirectional"))
      (node (ref "ETH_INT3") (pin "1") (pinfunction "1-TRANS+_1") (pintype "bidirectional"))
    )
    (net (code "82") (name "Net-(ETH_EXT3-2-TRANS-)") (class "Default")
      (node (ref "ETH_EXT3") (pin "2") (pinfunction "2-TRANS-_2") (pintype "bidirectional"))
      (node (ref "ETH_INT3") (pin "2") (pinfunction "2-TRANS-_2") (pintype "bidirectional"))
    )
    (net (code "83") (name "Net-(ETH_EXT3-3+RECEIVE+)") (class "Default")
      (node (ref "ETH_EXT3") (pin "3") (pinfunction "3+RECEIVE+_3") (pintype "bidirectional"))
      (node (ref "ETH_INT3") (pin "3") (pinfunction "3+RECEIVE+_3") (pintype "bidirectional"))
    )
    (net (code "84") (name "Net-(ETH_EXT3-6-RECEIVE-)") (class "Default")
      (node (ref "ETH_EXT3") (pin "6") (pinfunction "6-RECEIVE-_6") (pintype "bidirectional"))
      (node (ref "ETH_INT3") (pin "6") (pinfunction "6-RECEIVE-_6") (pintype "bidirectional"))
    )
    (net (code "85") (name "Net-(ETH_EXT4-1-TRANS+)") (class "Default")
      (node (ref "ETH_EXT4") (pin "1") (pinfunction "1-TRANS+_1") (pintype "bidirectional"))
      (node (ref "ETH_INT4") (pin "1") (pinfunction "1-TRANS+_1") (pintype "bidirectional"))
    )
    (net (code "86") (name "Net-(ETH_EXT4-2-TRANS-)") (class "Default")
      (node (ref "ETH_EXT4") (pin "2") (pinfunction "2-TRANS-_2") (pintype "bidirectional"))
      (node (ref "ETH_INT4") (pin "2") (pinfunction "2-TRANS-_2") (pintype "bidirectional"))
    )
    (net (code "87") (name "Net-(ETH_EXT4-3+RECEIVE+)") (class "Default")
      (node (ref "ETH_EXT4") (pin "3") (pinfunction "3+RECEIVE+_3") (pintype "bidirectional"))
      (node (ref "ETH_INT4") (pin "3") (pinfunction "3+RECEIVE+_3") (pintype "bidirectional"))
    )
    (net (code "88") (name "Net-(ETH_EXT4-6-RECEIVE-)") (class "Default")
      (node (ref "ETH_EXT4") (pin "6") (pinfunction "6-RECEIVE-_6") (pintype "bidirectional"))
      (node (ref "ETH_INT4") (pin "6") (pinfunction "6-RECEIVE-_6") (pintype "bidirectional"))
    )
    (net (code "89") (name "Net-(ETH_EXT5-1-TRANS+)") (class "Default")
      (node (ref "ETH_EXT5") (pin "1") (pinfunction "1-TRANS+_1") (pintype "bidirectional"))
      (node (ref "ETH_INT5") (pin "1") (pinfunction "1-TRANS+_1") (pintype "bidirectional"))
    )
    (net (code "90") (name "Net-(ETH_EXT5-2-TRANS-)") (class "Default")
      (node (ref "ETH_EXT5") (pin "2") (pinfunction "2-TRANS-_2") (pintype "bidirectional"))
      (node (ref "ETH_INT5") (pin "2") (pinfunction "2-TRANS-_2") (pintype "bidirectional"))
    )
    (net (code "91") (name "Net-(ETH_EXT5-3+RECEIVE+)") (class "Default")
      (node (ref "ETH_EXT5") (pin "3") (pinfunction "3+RECEIVE+_3") (pintype "bidirectional"))
      (node (ref "ETH_INT5") (pin "3") (pinfunction "3+RECEIVE+_3") (pintype "bidirectional"))
    )
    (net (code "92") (name "Net-(ETH_EXT5-6-RECEIVE-)") (class "Default")
      (node (ref "ETH_EXT5") (pin "6") (pinfunction "6-RECEIVE-_6") (pintype "bidirectional"))
      (node (ref "ETH_INT5") (pin "6") (pinfunction "6-RECEIVE-_6") (pintype "bidirectional"))
    )
    (net (code "93") (name "Net-(ETH_EXT6-1-TRANS+)") (class "Default")
      (node (ref "ETH_EXT6") (pin "1") (pinfunction "1-TRANS+_1") (pintype "bidirectional"))
      (node (ref "ETH_INT6") (pin "1") (pinfunction "1-TRANS+_1") (pintype "bidirectional"))
    )
    (net (code "94") (name "Net-(ETH_EXT6-2-TRANS-)") (class "Default")
      (node (ref "ETH_EXT6") (pin "2") (pinfunction "2-TRANS-_2") (pintype "bidirectional"))
      (node (ref "ETH_INT6") (pin "2") (pinfunction "2-TRANS-_2") (pintype "bidirectional"))
    )
    (net (code "95") (name "Net-(ETH_EXT6-3+RECEIVE+)") (class "Default")
      (node (ref "ETH_EXT6") (pin "3") (pinfunction "3+RECEIVE+_3") (pintype "bidirectional"))
      (node (ref "ETH_INT6") (pin "3") (pinfunction "3+RECEIVE+_3") (pintype "bidirectional"))
    )
    (net (code "96") (name "Net-(ETH_EXT6-6-RECEIVE-)") (class "Default")
      (node (ref "ETH_EXT6") (pin "6") (pinfunction "6-RECEIVE-_6") (pintype "bidirectional"))
      (node (ref "ETH_INT6") (pin "6") (pinfunction "6-RECEIVE-_6") (pintype "bidirectional"))
    )
    (net (code "97") (name "Net-(ETH_EXT7-1-TRANS+)") (class "Default")
      (node (ref "ETH_EXT7") (pin "1") (pinfunction "1-TRANS+_1") (pintype "bidirectional"))
      (node (ref "ETH_INT7") (pin "1") (pinfunction "1-TRANS+_1") (pintype "bidirectional"))
    )
    (net (code "98") (name "Net-(ETH_EXT7-2-TRANS-)") (class "Default")
      (node (ref "ETH_EXT7") (pin "2") (pinfunction "2-TRANS-_2") (pintype "bidirectional"))
      (node (ref "ETH_INT7") (pin "2") (pinfunction "2-TRANS-_2") (pintype "bidirectional"))
    )
    (net (code "99") (name "Net-(ETH_EXT7-3+RECEIVE+)") (class "Default")
      (node (ref "ETH_EXT7") (pin "3") (pinfunction "3+RECEIVE+_3") (pintype "bidirectional"))
      (node (ref "ETH_INT7") (pin "3") (pinfunction "3+RECEIVE+_3") (pintype "bidirectional"))
    )
    (net (code "100") (name "Net-(ETH_EXT7-4-DC+)") (class "Default")
      (node (ref "12V_CRITICAL") (pin "L") (pinfunction "L_L") (pintype "bidirectional"))
      (node (ref "ETH_EXT7") (pin "4") (pinfunction "4-DC+_4") (pintype "bidirectional"))
      (node (ref "ETH_EXT7") (pin "5") (pinfunction "5-DC++_5") (pintype "bidirectional"))
    )
    (net (code "101") (name "Net-(ETH_EXT7-6-RECEIVE-)") (class "Default")
      (node (ref "ETH_EXT7") (pin "6") (pinfunction "6-RECEIVE-_6") (pintype "bidirectional"))
      (node (ref "ETH_INT7") (pin "6") (pinfunction "6-RECEIVE-_6") (pintype "bidirectional"))
    )
    (net (code "102") (name "Net-(ETH_EXT7-7-DC--)") (class "Default")
      (node (ref "12V_CRITICAL") (pin "R") (pinfunction "R_R") (pintype "bidirectional"))
      (node (ref "ETH_EXT7") (pin "7") (pinfunction "7-DC--_7") (pintype "bidirectional"))
      (node (ref "ETH_EXT7") (pin "8") (pinfunction "8-DC-_8") (pintype "bidirectional"))
    )
    (net (code "103") (name "Net-(EXT_MOTOR_1-+)") (class "Default")
      (node (ref "EXT_MOTOR_1") (pin "POS") (pinfunction "+_POS") (pintype "bidirectional"))
      (node (ref "INT_MOTOR_1") (pin "L1") (pinfunction "L_L1") (pintype "bidirectional"))
      (node (ref "INT_MOTOR_1") (pin "L2") (pinfunction "L_L2") (pintype "bidirectional"))
    )
    (net (code "104") (name "Net-(EXT_MOTOR_1--)") (class "Default")
      (node (ref "EXT_MOTOR_1") (pin "NEG") (pinfunction "-_NEG") (pintype "bidirectional"))
      (node (ref "INT_MOTOR_1") (pin "R1") (pinfunction "R_R1") (pintype "bidirectional"))
      (node (ref "INT_MOTOR_1") (pin "R2") (pinfunction "R_R2") (pintype "bidirectional"))
    )
    (net (code "105") (name "Net-(EXT_MOTOR_2-+)") (class "Default")
      (node (ref "EXT_MOTOR_2") (pin "POS") (pinfunction "+_POS") (pintype "bidirectional"))
      (node (ref "INT_MOTOR_2") (pin "L1") (pinfunction "L_L1") (pintype "bidirectional"))
      (node (ref "INT_MOTOR_2") (pin "L2") (pinfunction "L_L2") (pintype "bidirectional"))
    )
    (net (code "106") (name "Net-(EXT_MOTOR_2--)") (class "Default")
      (node (ref "EXT_MOTOR_2") (pin "NEG") (pinfunction "-_NEG") (pintype "bidirectional"))
      (node (ref "INT_MOTOR_2") (pin "R1") (pinfunction "R_R1") (pintype "bidirectional"))
      (node (ref "INT_MOTOR_2") (pin "R2") (pinfunction "R_R2") (pintype "bidirectional"))
    )
    (net (code "107") (name "Net-(EXT_MOTOR_3-+)") (class "Default")
      (node (ref "EXT_MOTOR_3") (pin "POS") (pinfunction "+_POS") (pintype "bidirectional"))
      (node (ref "INT_MOTOR_3") (pin "L1") (pinfunction "L_L1") (pintype "bidirectional"))
      (node (ref "INT_MOTOR_3") (pin "L2") (pinfunction "L_L2") (pintype "bidirectional"))
    )
    (net (code "108") (name "Net-(EXT_MOTOR_3--)") (class "Default")
      (node (ref "EXT_MOTOR_3") (pin "NEG") (pinfunction "-_NEG") (pintype "bidirectional"))
      (node (ref "INT_MOTOR_3") (pin "R1") (pinfunction "R_R1") (pintype "bidirectional"))
      (node (ref "INT_MOTOR_3") (pin "R2") (pinfunction "R_R2") (pintype "bidirectional"))
    )
    (net (code "109") (name "Net-(EXT_MOTOR_4-+)") (class "Default")
      (node (ref "EXT_MOTOR_4") (pin "POS") (pinfunction "+_POS") (pintype "bidirectional"))
      (node (ref "INT_MOTOR_4") (pin "L1") (pinfunction "L_L1") (pintype "bidirectional"))
      (node (ref "INT_MOTOR_4") (pin "L2") (pinfunction "L_L2") (pintype "bidirectional"))
    )
    (net (code "110") (name "Net-(EXT_MOTOR_4--)") (class "Default")
      (node (ref "EXT_MOTOR_4") (pin "NEG") (pinfunction "-_NEG") (pintype "bidirectional"))
      (node (ref "INT_MOTOR_4") (pin "R1") (pinfunction "R_R1") (pintype "bidirectional"))
      (node (ref "INT_MOTOR_4") (pin "R2") (pinfunction "R_R2") (pintype "bidirectional"))
    )
    (net (code "111") (name "Net-(EXT_MOTOR_5-+)") (class "Default")
      (node (ref "EXT_MOTOR_5") (pin "POS") (pinfunction "+_POS") (pintype "bidirectional"))
      (node (ref "INT_MOTOR_5") (pin "L1") (pinfunction "L_L1") (pintype "bidirectional"))
      (node (ref "INT_MOTOR_5") (pin "L2") (pinfunction "L_L2") (pintype "bidirectional"))
    )
    (net (code "112") (name "Net-(EXT_MOTOR_5--)") (class "Default")
      (node (ref "EXT_MOTOR_5") (pin "NEG") (pinfunction "-_NEG") (pintype "bidirectional"))
      (node (ref "INT_MOTOR_5") (pin "R1") (pinfunction "R_R1") (pintype "bidirectional"))
      (node (ref "INT_MOTOR_5") (pin "R2") (pinfunction "R_R2") (pintype "bidirectional"))
    )
    (net (code "113") (name "Net-(EXT_MOTOR_6-+)") (class "Default")
      (node (ref "EXT_MOTOR_6") (pin "POS") (pinfunction "+_POS") (pintype "bidirectional"))
      (node (ref "INT_MOTOR_6") (pin "L1") (pinfunction "L_L1") (pintype "bidirectional"))
      (node (ref "INT_MOTOR_6") (pin "L2") (pinfunction "L_L2") (pintype "bidirectional"))
    )
    (net (code "114") (name "Net-(EXT_MOTOR_6--)") (class "Default")
      (node (ref "EXT_MOTOR_6") (pin "NEG") (pinfunction "-_NEG") (pintype "bidirectional"))
      (node (ref "INT_MOTOR_6") (pin "R1") (pinfunction "R_R1") (pintype "bidirectional"))
      (node (ref "INT_MOTOR_6") (pin "R2") (pinfunction "R_R2") (pintype "bidirectional"))
    )
    (net (code "115") (name "V+") (class "Default")
      (node (ref "12V_HIGH_POWER") (pin "L1") (pinfunction "L_L1") (pintype "bidirectional"))
      (node (ref "12V_HIGH_POWER") (pin "L2") (pinfunction "L_L2") (pintype "bidirectional"))
      (node (ref "U$1") (pin "P$2") (pinfunction "P$2_P$2") (pintype "bidirectional"))
      (node (ref "U$2") (pin "P$2") (pinfunction "P$2_P$2") (pintype "bidirectional"))
      (node (ref "U$3") (pin "P$2") (pinfunction "P$2_P$2") (pintype "bidirectional"))
      (node (ref "U$5") (pin "P$2") (pinfunction "P$2_P$2") (pintype "bidirectional"))
      (node (ref "U$6") (pin "P$2") (pinfunction "P$2_P$2") (pintype "bidirectional"))
      (node (ref "U$8") (pin "P$2") (pinfunction "P$2_P$2") (pintype "bidirectional"))
    )
    (net (code "116") (name "unconnected-(ETH_INT1-4-DC+-Pad4)") (class "Default")
      (node (ref "ETH_INT1") (pin "4") (pinfunction "4-DC+_4") (pintype "bidirectional"))
    )
    (net (code "117") (name "unconnected-(ETH_INT1-5-DC++-Pad5)") (class "Default")
      (node (ref "ETH_INT1") (pin "5") (pinfunction "5-DC++_5") (pintype "bidirectional"))
    )
    (net (code "118") (name "unconnected-(ETH_INT1-7-DC---Pad7)") (class "Default")
      (node (ref "ETH_INT1") (pin "7") (pinfunction "7-DC--_7") (pintype "bidirectional"))
    )
    (net (code "119") (name "unconnected-(ETH_INT1-8-DC--Pad8)") (class "Default")
      (node (ref "ETH_INT1") (pin "8") (pinfunction "8-DC-_8") (pintype "bidirectional"))
    )
    (net (code "120") (name "unconnected-(ETH_INT2-4-DC+-Pad4)") (class "Default")
      (node (ref "ETH_INT2") (pin "4") (pinfunction "4-DC+_4") (pintype "bidirectional"))
    )
    (net (code "121") (name "unconnected-(ETH_INT2-5-DC++-Pad5)") (class "Default")
      (node (ref "ETH_INT2") (pin "5") (pinfunction "5-DC++_5") (pintype "bidirectional"))
    )
    (net (code "122") (name "unconnected-(ETH_INT2-7-DC---Pad7)") (class "Default")
      (node (ref "ETH_INT2") (pin "7") (pinfunction "7-DC--_7") (pintype "bidirectional"))
    )
    (net (code "123") (name "unconnected-(ETH_INT2-8-DC--Pad8)") (class "Default")
      (node (ref "ETH_INT2") (pin "8") (pinfunction "8-DC-_8") (pintype "bidirectional"))
    )
    (net (code "124") (name "unconnected-(ETH_INT3-4-DC+-Pad4)") (class "Default")
      (node (ref "ETH_INT3") (pin "4") (pinfunction "4-DC+_4") (pintype "bidirectional"))
    )
    (net (code "125") (name "unconnected-(ETH_INT3-5-DC++-Pad5)") (class "Default")
      (node (ref "ETH_INT3") (pin "5") (pinfunction "5-DC++_5") (pintype "bidirectional"))
    )
    (net (code "126") (name "unconnected-(ETH_INT3-7-DC---Pad7)") (class "Default")
      (node (ref "ETH_INT3") (pin "7") (pinfunction "7-DC--_7") (pintype "bidirectional"))
    )
    (net (code "127") (name "unconnected-(ETH_INT3-8-DC--Pad8)") (class "Default")
      (node (ref "ETH_INT3") (pin "8") (pinfunction "8-DC-_8") (pintype "bidirectional"))
    )
    (net (code "128") (name "unconnected-(ETH_INT4-4-DC+-Pad4)") (class "Default")
      (node (ref "ETH_INT4") (pin "4") (pinfunction "4-DC+_4") (pintype "bidirectional"))
    )
    (net (code "129") (name "unconnected-(ETH_INT4-5-DC++-Pad5)") (class "Default")
      (node (ref "ETH_INT4") (pin "5") (pinfunction "5-DC++_5") (pintype "bidirectional"))
    )
    (net (code "130") (name "unconnected-(ETH_INT4-7-DC---Pad7)") (class "Default")
      (node (ref "ETH_INT4") (pin "7") (pinfunction "7-DC--_7") (pintype "bidirectional"))
    )
    (net (code "131") (name "unconnected-(ETH_INT4-8-DC--Pad8)") (class "Default")
      (node (ref "ETH_INT4") (pin "8") (pinfunction "8-DC-_8") (pintype "bidirectional"))
    )
    (net (code "132") (name "unconnected-(ETH_INT5-4-DC+-Pad4)") (class "Default")
      (node (ref "ETH_INT5") (pin "4") (pinfunction "4-DC+_4") (pintype "bidirectional"))
    )
    (net (code "133") (name "unconnected-(ETH_INT5-5-DC++-Pad5)") (class "Default")
      (node (ref "ETH_INT5") (pin "5") (pinfunction "5-DC++_5") (pintype "bidirectional"))
    )
    (net (code "134") (name "unconnected-(ETH_INT5-7-DC---Pad7)") (class "Default")
      (node (ref "ETH_INT5") (pin "7") (pinfunction "7-DC--_7") (pintype "bidirectional"))
    )
    (net (code "135") (name "unconnected-(ETH_INT5-8-DC--Pad8)") (class "Default")
      (node (ref "ETH_INT5") (pin "8") (pinfunction "8-DC-_8") (pintype "bidirectional"))
    )
    (net (code "136") (name "unconnected-(ETH_INT6-4-DC+-Pad4)") (class "Default")
      (node (ref "ETH_INT6") (pin "4") (pinfunction "4-DC+_4") (pintype "bidirectional"))
    )
    (net (code "137") (name "unconnected-(ETH_INT6-5-DC++-Pad5)") (class "Default")
      (node (ref "ETH_INT6") (pin "5") (pinfunction "5-DC++_5") (pintype "bidirectional"))
    )
    (net (code "138") (name "unconnected-(ETH_INT6-7-DC---Pad7)") (class "Default")
      (node (ref "ETH_INT6") (pin "7") (pinfunction "7-DC--_7") (pintype "bidirectional"))
    )
    (net (code "139") (name "unconnected-(ETH_INT6-8-DC--Pad8)") (class "Default")
      (node (ref "ETH_INT6") (pin "8") (pinfunction "8-DC-_8") (pintype "bidirectional"))
    )
    (net (code "140") (name "unconnected-(ETH_INT7-4-DC+-Pad4)") (class "Default")
      (node (ref "ETH_INT7") (pin "4") (pinfunction "4-DC+_4") (pintype "bidirectional"))
    )
    (net (code "141") (name "unconnected-(ETH_INT7-5-DC++-Pad5)") (class "Default")
      (node (ref "ETH_INT7") (pin "5") (pinfunction "5-DC++_5") (pintype "bidirectional"))
    )
    (net (code "142") (name "unconnected-(ETH_INT7-7-DC---Pad7)") (class "Default")
      (node (ref "ETH_INT7") (pin "7") (pinfunction "7-DC--_7") (pintype "bidirectional"))
    )
    (net (code "143") (name "unconnected-(ETH_INT7-8-DC--Pad8)") (class "Default")
      (node (ref "ETH_INT7") (pin "8") (pinfunction "8-DC-_8") (pintype "bidirectional"))
    )
  )
)
